# fpga_eagle_1.net
KiCad netlist of a schematic drawn in Altium Designer
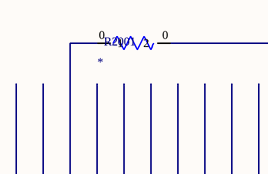
[diagram p0: fpga_eagle_1.SchDoc, top left]
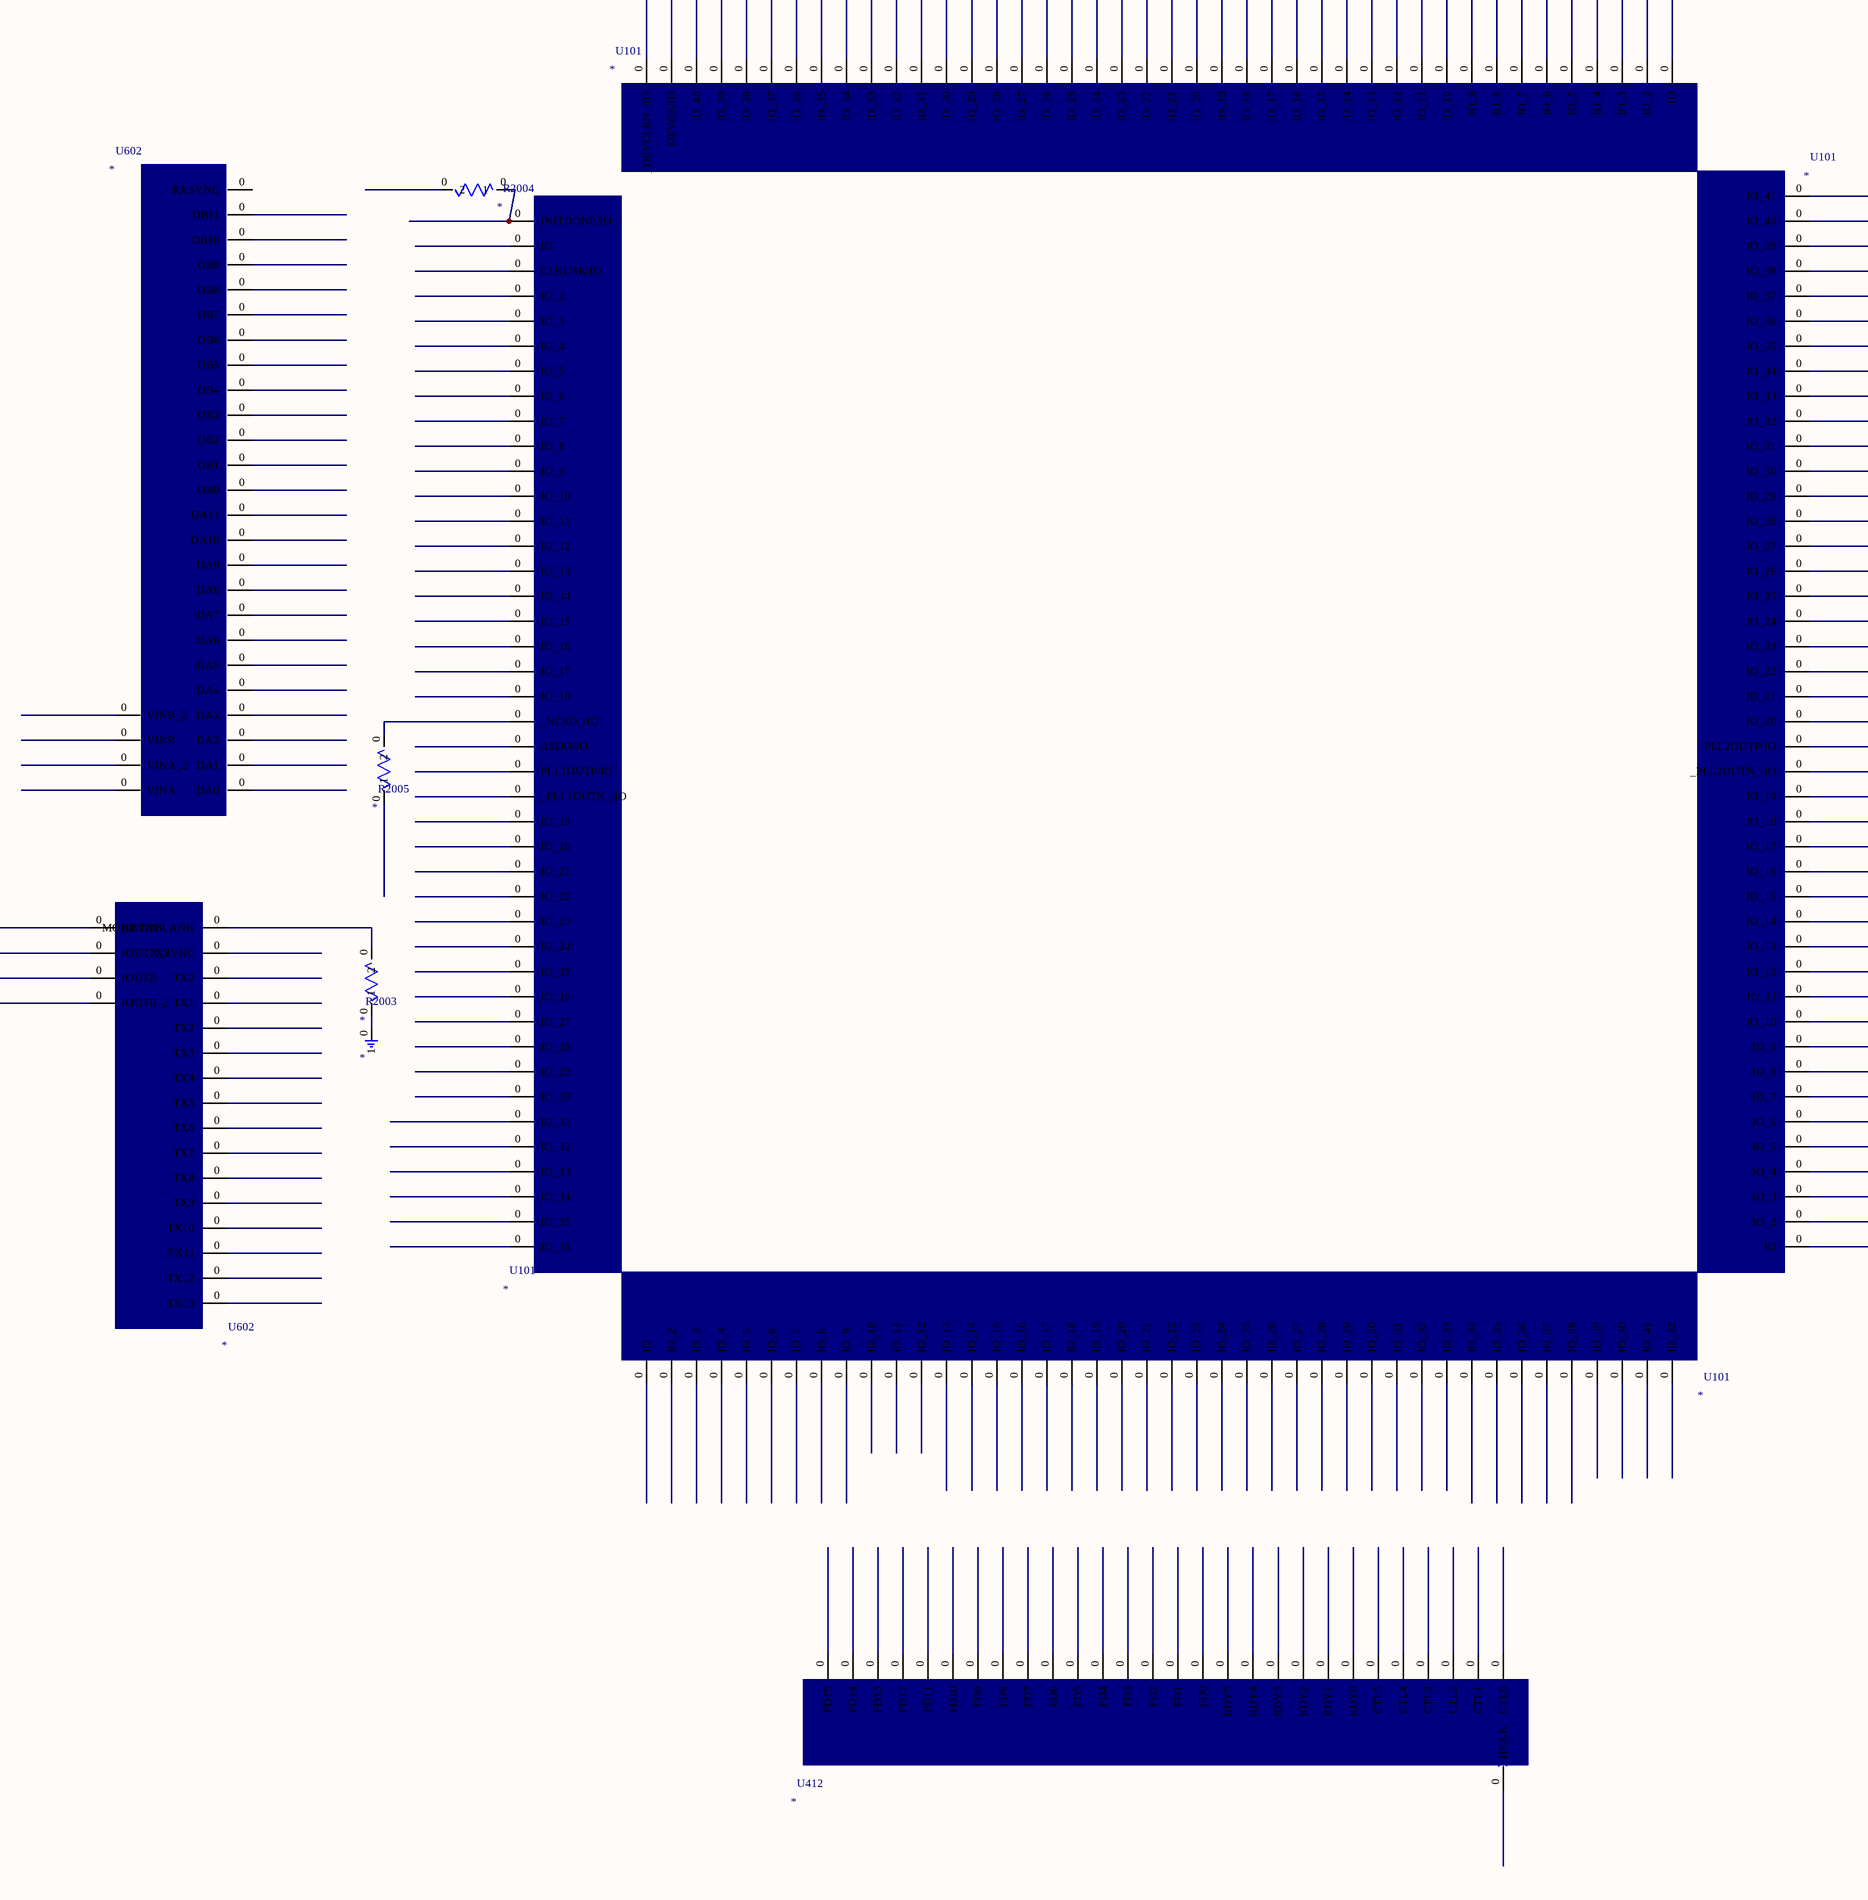
[diagram p1: fpga_eagle_1.SchDoc, bottom left]
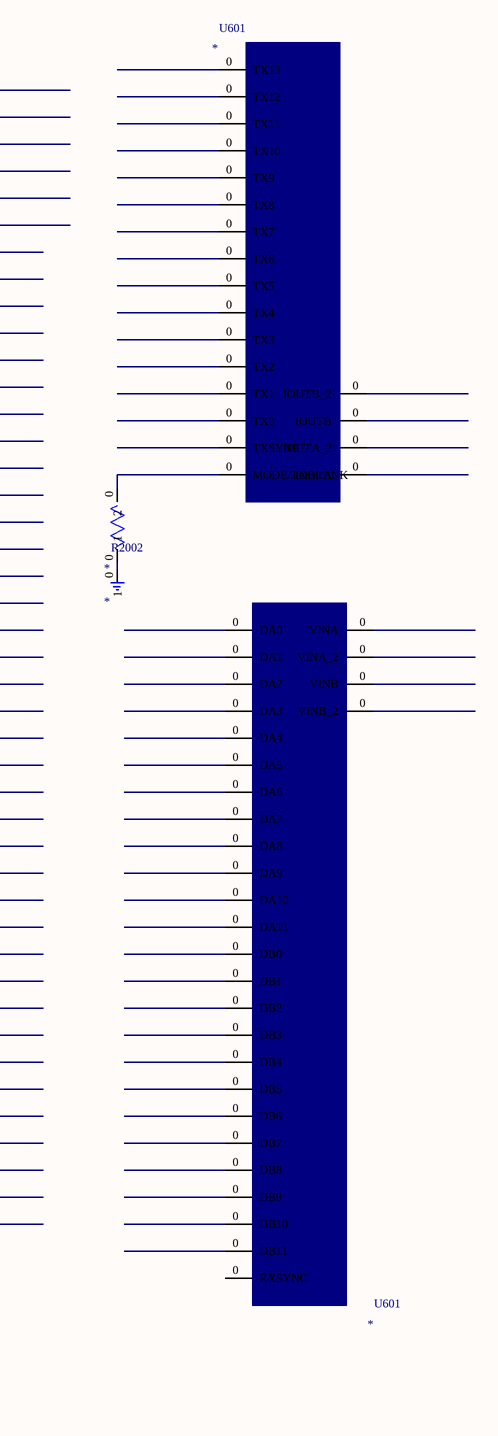
[diagram p2: fpga_eagle_1.SchDoc, bottom right]

(export (version "E")
  (design (tool "Eeschema 10.0.6"))
  (components
    (comp (ref "GND-1") (value "*") (libsource (lib "openjson") (part "GND-1")))
    (comp (ref "GND-1-5") (value "*") (libsource (lib "openjson") (part "GND-1")))
    (comp (ref "R2001") (value "*") (libsource (lib "openjson") (part "RESISTOR-1")))
    (comp (ref "R2002") (value "*") (libsource (lib "") (part "RESISTOR-1_MIRRORED_2")))
    (comp (ref "R2003") (value "*") (libsource (lib "") (part "RESISTOR-1_MIRRORED_3")))
    (comp (ref "R2004") (value "*") (libsource (lib "openjson") (part "RESISTOR-1_MIRRORED")))
    (comp (ref "R2005") (value "*") (libsource (lib "") (part "RESISTOR-1_MIRRORED_1")))
    (comp (ref "U101") (value "*") (libsource (lib "openjson") (part "EP1C12-PQ240-IO1")))
    (comp (ref "U101-1") (value "*") (libsource (lib "openjson") (part "EP1C12-PQ240-IO2")))
    (comp (ref "U101-2") (value "*") (libsource (lib "openjson") (part "EP1C12-PQ240-IO3")))
    (comp (ref "U101-3") (value "*") (libsource (lib "openjson") (part "EP1C12-PQ240-IO4")))
    (comp (ref "U412") (value "*") (libsource (lib "openjson") (part "CY7C68013-TQ100-BUS_MIRRORED")))
    (comp (ref "U601") (value "*") (libsource (lib "openjson") (part "AD986X-RX_MIRRORED")))
    (comp (ref "U601-0") (value "*") (libsource (lib "openjson") (part "AD986X-TX_MIRRORED")))
    (comp (ref "U602") (value "*") (libsource (lib "") (part "AD986X-RX_MIRRORED_1")))
    (comp (ref "U602-4") (value "*") (libsource (lib "") (part "AD986X-TX_MIRRORED_1")))
  )
  (nets
    (net (code "1") (name "Net-(GND-1-1)") (class "Default")
      (node (ref "GND-1") (pin "0") (pinfunction "1_0") (pintype "passive"))
      (node (ref "R2003") (pin "0") (pinfunction "1_0") (pintype "passive"))
    )
    (net (code "2") (name "Net-(GND-1-5-1)") (class "Default")
      (node (ref "GND-1-5") (pin "0") (pinfunction "1_0") (pintype "passive"))
      (node (ref "R2002") (pin "0") (pinfunction "1_0") (pintype "passive"))
    )
    (net (code "3") (name "Net-(R2001-1)") (class "Default")
      (node (ref "R2001") (pin "0") (pinfunction "1_0") (pintype "passive"))
      (node (ref "U101-1") (pin "0") (pinfunction "IO_10_0") (pintype "passive"))
    )
    (net (code "4") (name "Net-(R2002-2)") (class "Default")
      (node (ref "R2002") (pin "0") (pinfunction "2_0") (pintype "passive"))
      (node (ref "U601-0") (pin "0") (pinfunction "MODE/TXBLANK_0") (pintype "passive"))
    )
    (net (code "5") (name "Net-(R2003-2)") (class "Default")
      (node (ref "R2003") (pin "0") (pinfunction "2_0") (pintype "passive"))
      (node (ref "U602-4") (pin "0") (pinfunction "MODE/TXBLANK_0") (pintype "passive"))
    )
    (net (code "6") (name "Net-(R2004-1)") (class "Default")
      (node (ref "R2004") (pin "0") (pinfunction "1_0") (pintype "passive"))
      (node (ref "U101") (pin "0") (pinfunction "INITDONE/IO_0") (pintype "passive"))
    )
    (net (code "7") (name "Net-(R2005-2)") (class "Default")
      (node (ref "R2005") (pin "0") (pinfunction "2_0") (pintype "passive"))
      (node (ref "U101") (pin "0") (pinfunction "_NCSO_/IO_0") (pintype "passive"))
    )
    (net (code "8") (name "unconnected-(R2001-2-Pad0)") (class "Default")
      (node (ref "R2001") (pin "0") (pinfunction "2_0") (pintype "passive"))
    )
    (net (code "9") (name "unconnected-(R2004-2-Pad0)") (class "Default")
      (node (ref "R2004") (pin "0") (pinfunction "2_0") (pintype "passive"))
    )
    (net (code "10") (name "unconnected-(R2005-1-Pad0)") (class "Default")
      (node (ref "R2005") (pin "0") (pinfunction "1_0") (pintype "passive"))
    )
    (net (code "11") (name "unconnected-(U101-1-DEVOE{slash}IO-Pad0)") (class "Default")
      (node (ref "U101-1") (pin "0") (pinfunction "DEVOE/IO_0") (pintype "passive"))
    )
    (net (code "12") (name "unconnected-(U101-1-IO-Pad0)") (class "Default")
      (node (ref "U101-1") (pin "0") (pinfunction "IO_0") (pintype "passive"))
    )
    (net (code "13") (name "unconnected-(U101-1-IO_2-Pad0)") (class "Default")
      (node (ref "U101-1") (pin "0") (pinfunction "IO_2_0") (pintype "passive"))
    )
    (net (code "14") (name "unconnected-(U101-1-IO_3-Pad0)") (class "Default")
      (node (ref "U101-1") (pin "0") (pinfunction "IO_3_0") (pintype "passive"))
    )
    (net (code "15") (name "unconnected-(U101-1-IO_4-Pad0)") (class "Default")
      (node (ref "U101-1") (pin "0") (pinfunction "IO_4_0") (pintype "passive"))
    )
    (net (code "16") (name "unconnected-(U101-1-IO_5-Pad0)") (class "Default")
      (node (ref "U101-1") (pin "0") (pinfunction "IO_5_0") (pintype "passive"))
    )
    (net (code "17") (name "unconnected-(U101-1-IO_6-Pad0)") (class "Default")
      (node (ref "U101-1") (pin "0") (pinfunction "IO_6_0") (pintype "passive"))
    )
    (net (code "18") (name "unconnected-(U101-1-IO_7-Pad0)") (class "Default")
      (node (ref "U101-1") (pin "0") (pinfunction "IO_7_0") (pintype "passive"))
    )
    (net (code "19") (name "unconnected-(U101-1-IO_8-Pad0)") (class "Default")
      (node (ref "U101-1") (pin "0") (pinfunction "IO_8_0") (pintype "passive"))
    )
    (net (code "20") (name "unconnected-(U101-1-IO_9-Pad0)") (class "Default")
      (node (ref "U101-1") (pin "0") (pinfunction "IO_9_0") (pintype "passive"))
    )
    (net (code "21") (name "unconnected-(U101-1-IO_11-Pad0)") (class "Default")
      (node (ref "U101-1") (pin "0") (pinfunction "IO_11_0") (pintype "passive"))
    )
    (net (code "22") (name "unconnected-(U101-1-IO_12-Pad0)") (class "Default")
      (node (ref "U101-1") (pin "0") (pinfunction "IO_12_0") (pintype "passive"))
    )
    (net (code "23") (name "unconnected-(U101-1-IO_13-Pad0)") (class "Default")
      (node (ref "U101-1") (pin "0") (pinfunction "IO_13_0") (pintype "passive"))
    )
    (net (code "24") (name "unconnected-(U101-1-IO_14-Pad0)") (class "Default")
      (node (ref "U101-1") (pin "0") (pinfunction "IO_14_0") (pintype "passive"))
    )
    (net (code "25") (name "unconnected-(U101-1-IO_15-Pad0)") (class "Default")
      (node (ref "U101-1") (pin "0") (pinfunction "IO_15_0") (pintype "passive"))
    )
    (net (code "26") (name "unconnected-(U101-1-IO_16-Pad0)") (class "Default")
      (node (ref "U101-1") (pin "0") (pinfunction "IO_16_0") (pintype "passive"))
    )
    (net (code "27") (name "unconnected-(U101-1-IO_17-Pad0)") (class "Default")
      (node (ref "U101-1") (pin "0") (pinfunction "IO_17_0") (pintype "passive"))
    )
    (net (code "28") (name "unconnected-(U101-1-IO_18-Pad0)") (class "Default")
      (node (ref "U101-1") (pin "0") (pinfunction "IO_18_0") (pintype "passive"))
    )
    (net (code "29") (name "unconnected-(U101-1-IO_19-Pad0)") (class "Default")
      (node (ref "U101-1") (pin "0") (pinfunction "IO_19_0") (pintype "passive"))
    )
    (net (code "30") (name "unconnected-(U101-1-IO_20-Pad0)") (class "Default")
      (node (ref "U101-1") (pin "0") (pinfunction "IO_20_0") (pintype "passive"))
    )
    (net (code "31") (name "unconnected-(U101-1-IO_21-Pad0)") (class "Default")
      (node (ref "U101-1") (pin "0") (pinfunction "IO_21_0") (pintype "passive"))
    )
    (net (code "32") (name "unconnected-(U101-1-IO_22-Pad0)") (class "Default")
      (node (ref "U101-1") (pin "0") (pinfunction "IO_22_0") (pintype "passive"))
    )
    (net (code "33") (name "unconnected-(U101-1-IO_23-Pad0)") (class "Default")
      (node (ref "U101-1") (pin "0") (pinfunction "IO_23_0") (pintype "passive"))
    )
    (net (code "34") (name "unconnected-(U101-1-IO_24-Pad0)") (class "Default")
      (node (ref "U101-1") (pin "0") (pinfunction "IO_24_0") (pintype "passive"))
    )
    (net (code "35") (name "unconnected-(U101-1-IO_25-Pad0)") (class "Default")
      (node (ref "U101-1") (pin "0") (pinfunction "IO_25_0") (pintype "passive"))
    )
    (net (code "36") (name "unconnected-(U101-1-IO_26-Pad0)") (class "Default")
      (node (ref "U101-1") (pin "0") (pinfunction "IO_26_0") (pintype "passive"))
    )
    (net (code "37") (name "unconnected-(U101-1-IO_27-Pad0)") (class "Default")
      (node (ref "U101-1") (pin "0") (pinfunction "IO_27_0") (pintype "passive"))
    )
    (net (code "38") (name "unconnected-(U101-1-IO_28-Pad0)") (class "Default")
      (node (ref "U101-1") (pin "0") (pinfunction "IO_28_0") (pintype "passive"))
    )
    (net (code "39") (name "unconnected-(U101-1-IO_29-Pad0)") (class "Default")
      (node (ref "U101-1") (pin "0") (pinfunction "IO_29_0") (pintype "passive"))
    )
    (net (code "40") (name "unconnected-(U101-1-IO_30-Pad0)") (class "Default")
      (node (ref "U101-1") (pin "0") (pinfunction "IO_30_0") (pintype "passive"))
    )
    (net (code "41") (name "unconnected-(U101-1-IO_31-Pad0)") (class "Default")
      (node (ref "U101-1") (pin "0") (pinfunction "IO_31_0") (pintype "passive"))
    )
    (net (code "42") (name "unconnected-(U101-1-IO_32-Pad0)") (class "Default")
      (node (ref "U101-1") (pin "0") (pinfunction "IO_32_0") (pintype "passive"))
    )
    (net (code "43") (name "unconnected-(U101-1-IO_33-Pad0)") (class "Default")
      (node (ref "U101-1") (pin "0") (pinfunction "IO_33_0") (pintype "passive"))
    )
    (net (code "44") (name "unconnected-(U101-1-IO_34-Pad0)") (class "Default")
      (node (ref "U101-1") (pin "0") (pinfunction "IO_34_0") (pintype "passive"))
    )
    (net (code "45") (name "unconnected-(U101-1-IO_35-Pad0)") (class "Default")
      (node (ref "U101-1") (pin "0") (pinfunction "IO_35_0") (pintype "passive"))
    )
    (net (code "46") (name "unconnected-(U101-1-IO_36-Pad0)") (class "Default")
      (node (ref "U101-1") (pin "0") (pinfunction "IO_36_0") (pintype "passive"))
    )
    (net (code "47") (name "unconnected-(U101-1-IO_37-Pad0)") (class "Default")
      (node (ref "U101-1") (pin "0") (pinfunction "IO_37_0") (pintype "passive"))
    )
    (net (code "48") (name "unconnected-(U101-1-IO_38-Pad0)") (class "Default")
      (node (ref "U101-1") (pin "0") (pinfunction "IO_38_0") (pintype "passive"))
    )
    (net (code "49") (name "unconnected-(U101-1-IO_39-Pad0)") (class "Default")
      (node (ref "U101-1") (pin "0") (pinfunction "IO_39_0") (pintype "passive"))
    )
    (net (code "50") (name "unconnected-(U101-1-IO_40-Pad0)") (class "Default")
      (node (ref "U101-1") (pin "0") (pinfunction "IO_40_0") (pintype "passive"))
    )
    (net (code "51") (name "unconnected-(U101-1-_DE~{V}CLRN_{slash}IO-Pad0)") (class "Default")
      (node (ref "U101-1") (pin "0") (pinfunction "_DE~{V}CLRN_/IO_0") (pintype "passive"))
    )
    (net (code "52") (name "unconnected-(U101-2-IO-Pad0)") (class "Default")
      (node (ref "U101-2") (pin "0") (pinfunction "IO_0") (pintype "passive"))
    )
    (net (code "53") (name "unconnected-(U101-2-IO_2-Pad0)") (class "Default")
      (node (ref "U101-2") (pin "0") (pinfunction "IO_2_0") (pintype "passive"))
    )
    (net (code "54") (name "unconnected-(U101-2-IO_3-Pad0)") (class "Default")
      (node (ref "U101-2") (pin "0") (pinfunction "IO_3_0") (pintype "passive"))
    )
    (net (code "55") (name "unconnected-(U101-2-IO_4-Pad0)") (class "Default")
      (node (ref "U101-2") (pin "0") (pinfunction "IO_4_0") (pintype "passive"))
    )
    (net (code "56") (name "unconnected-(U101-2-IO_5-Pad0)") (class "Default")
      (node (ref "U101-2") (pin "0") (pinfunction "IO_5_0") (pintype "passive"))
    )
    (net (code "57") (name "unconnected-(U101-2-IO_6-Pad0)") (class "Default")
      (node (ref "U101-2") (pin "0") (pinfunction "IO_6_0") (pintype "passive"))
    )
    (net (code "58") (name "unconnected-(U101-2-IO_7-Pad0)") (class "Default")
      (node (ref "U101-2") (pin "0") (pinfunction "IO_7_0") (pintype "passive"))
    )
    (net (code "59") (name "unconnected-(U101-2-IO_8-Pad0)") (class "Default")
      (node (ref "U101-2") (pin "0") (pinfunction "IO_8_0") (pintype "passive"))
    )
    (net (code "60") (name "unconnected-(U101-2-IO_9-Pad0)") (class "Default")
      (node (ref "U101-2") (pin "0") (pinfunction "IO_9_0") (pintype "passive"))
    )
    (net (code "61") (name "unconnected-(U101-2-IO_10-Pad0)") (class "Default")
      (node (ref "U101-2") (pin "0") (pinfunction "IO_10_0") (pintype "passive"))
    )
    (net (code "62") (name "unconnected-(U101-2-IO_11-Pad0)") (class "Default")
      (node (ref "U101-2") (pin "0") (pinfunction "IO_11_0") (pintype "passive"))
    )
    (net (code "63") (name "unconnected-(U101-2-IO_12-Pad0)") (class "Default")
      (node (ref "U101-2") (pin "0") (pinfunction "IO_12_0") (pintype "passive"))
    )
    (net (code "64") (name "unconnected-(U101-2-IO_13-Pad0)") (class "Default")
      (node (ref "U101-2") (pin "0") (pinfunction "IO_13_0") (pintype "passive"))
    )
    (net (code "65") (name "unconnected-(U101-2-IO_14-Pad0)") (class "Default")
      (node (ref "U101-2") (pin "0") (pinfunction "IO_14_0") (pintype "passive"))
    )
    (net (code "66") (name "unconnected-(U101-2-IO_15-Pad0)") (class "Default")
      (node (ref "U101-2") (pin "0") (pinfunction "IO_15_0") (pintype "passive"))
    )
    (net (code "67") (name "unconnected-(U101-2-IO_16-Pad0)") (class "Default")
      (node (ref "U101-2") (pin "0") (pinfunction "IO_16_0") (pintype "passive"))
    )
    (net (code "68") (name "unconnected-(U101-2-IO_17-Pad0)") (class "Default")
      (node (ref "U101-2") (pin "0") (pinfunction "IO_17_0") (pintype "passive"))
    )
    (net (code "69") (name "unconnected-(U101-2-IO_18-Pad0)") (class "Default")
      (node (ref "U101-2") (pin "0") (pinfunction "IO_18_0") (pintype "passive"))
    )
    (net (code "70") (name "unconnected-(U101-2-IO_19-Pad0)") (class "Default")
      (node (ref "U101-2") (pin "0") (pinfunction "IO_19_0") (pintype "passive"))
    )
    (net (code "71") (name "unconnected-(U101-2-IO_20-Pad0)") (class "Default")
      (node (ref "U101-2") (pin "0") (pinfunction "IO_20_0") (pintype "passive"))
    )
    (net (code "72") (name "unconnected-(U101-2-IO_21-Pad0)") (class "Default")
      (node (ref "U101-2") (pin "0") (pinfunction "IO_21_0") (pintype "passive"))
    )
    (net (code "73") (name "unconnected-(U101-2-IO_22-Pad0)") (class "Default")
      (node (ref "U101-2") (pin "0") (pinfunction "IO_22_0") (pintype "passive"))
    )
    (net (code "74") (name "unconnected-(U101-2-IO_23-Pad0)") (class "Default")
      (node (ref "U101-2") (pin "0") (pinfunction "IO_23_0") (pintype "passive"))
    )
    (net (code "75") (name "unconnected-(U101-2-IO_24-Pad0)") (class "Default")
      (node (ref "U101-2") (pin "0") (pinfunction "IO_24_0") (pintype "passive"))
    )
    (net (code "76") (name "unconnected-(U101-2-IO_25-Pad0)") (class "Default")
      (node (ref "U101-2") (pin "0") (pinfunction "IO_25_0") (pintype "passive"))
    )
    (net (code "77") (name "unconnected-(U101-2-IO_26-Pad0)") (class "Default")
      (node (ref "U101-2") (pin "0") (pinfunction "IO_26_0") (pintype "passive"))
    )
    (net (code "78") (name "unconnected-(U101-2-IO_27-Pad0)") (class "Default")
      (node (ref "U101-2") (pin "0") (pinfunction "IO_27_0") (pintype "passive"))
    )
    (net (code "79") (name "unconnected-(U101-2-IO_28-Pad0)") (class "Default")
      (node (ref "U101-2") (pin "0") (pinfunction "IO_28_0") (pintype "passive"))
    )
    (net (code "80") (name "unconnected-(U101-2-IO_29-Pad0)") (class "Default")
      (node (ref "U101-2") (pin "0") (pinfunction "IO_29_0") (pintype "passive"))
    )
    (net (code "81") (name "unconnected-(U101-2-IO_30-Pad0)") (class "Default")
      (node (ref "U101-2") (pin "0") (pinfunction "IO_30_0") (pintype "passive"))
    )
    (net (code "82") (name "unconnected-(U101-2-IO_31-Pad0)") (class "Default")
      (node (ref "U101-2") (pin "0") (pinfunction "IO_31_0") (pintype "passive"))
    )
    (net (code "83") (name "unconnected-(U101-2-IO_32-Pad0)") (class "Default")
      (node (ref "U101-2") (pin "0") (pinfunction "IO_32_0") (pintype "passive"))
    )
    (net (code "84") (name "unconnected-(U101-2-IO_33-Pad0)") (class "Default")
      (node (ref "U101-2") (pin "0") (pinfunction "IO_33_0") (pintype "passive"))
    )
    (net (code "85") (name "unconnected-(U101-2-IO_34-Pad0)") (class "Default")
      (node (ref "U101-2") (pin "0") (pinfunction "IO_34_0") (pintype "passive"))
    )
    (net (code "86") (name "unconnected-(U101-2-IO_35-Pad0)") (class "Default")
      (node (ref "U101-2") (pin "0") (pinfunction "IO_35_0") (pintype "passive"))
    )
    (net (code "87") (name "unconnected-(U101-2-IO_36-Pad0)") (class "Default")
      (node (ref "U101-2") (pin "0") (pinfunction "IO_36_0") (pintype "passive"))
    )
    (net (code "88") (name "unconnected-(U101-2-IO_37-Pad0)") (class "Default")
      (node (ref "U101-2") (pin "0") (pinfunction "IO_37_0") (pintype "passive"))
    )
    (net (code "89") (name "unconnected-(U101-2-IO_38-Pad0)") (class "Default")
      (node (ref "U101-2") (pin "0") (pinfunction "IO_38_0") (pintype "passive"))
    )
    (net (code "90") (name "unconnected-(U101-2-IO_39-Pad0)") (class "Default")
      (node (ref "U101-2") (pin "0") (pinfunction "IO_39_0") (pintype "passive"))
    )
    (net (code "91") (name "unconnected-(U101-2-IO_40-Pad0)") (class "Default")
      (node (ref "U101-2") (pin "0") (pinfunction "IO_40_0") (pintype "passive"))
    )
    (net (code "92") (name "unconnected-(U101-2-IO_41-Pad0)") (class "Default")
      (node (ref "U101-2") (pin "0") (pinfunction "IO_41_0") (pintype "passive"))
    )
    (net (code "93") (name "unconnected-(U101-2-PLL2OUTP{slash}IO-Pad0)") (class "Default")
      (node (ref "U101-2") (pin "0") (pinfunction "PLL2OUTP/IO_0") (pintype "passive"))
    )
    (net (code "94") (name "unconnected-(U101-2-_PLL2OUTN_{slash}IO-Pad0)") (class "Default")
      (node (ref "U101-2") (pin "0") (pinfunction "_PLL2OUTN_/IO_0") (pintype "passive"))
    )
    (net (code "95") (name "unconnected-(U101-3-IO-Pad0)") (class "Default")
      (node (ref "U101-3") (pin "0") (pinfunction "IO_0") (pintype "passive"))
    )
    (net (code "96") (name "unconnected-(U101-3-IO_2-Pad0)") (class "Default")
      (node (ref "U101-3") (pin "0") (pinfunction "IO_2_0") (pintype "passive"))
    )
    (net (code "97") (name "unconnected-(U101-3-IO_3-Pad0)") (class "Default")
      (node (ref "U101-3") (pin "0") (pinfunction "IO_3_0") (pintype "passive"))
    )
    (net (code "98") (name "unconnected-(U101-3-IO_4-Pad0)") (class "Default")
      (node (ref "U101-3") (pin "0") (pinfunction "IO_4_0") (pintype "passive"))
    )
    (net (code "99") (name "unconnected-(U101-3-IO_5-Pad0)") (class "Default")
      (node (ref "U101-3") (pin "0") (pinfunction "IO_5_0") (pintype "passive"))
    )
    (net (code "100") (name "unconnected-(U101-3-IO_6-Pad0)") (class "Default")
      (node (ref "U101-3") (pin "0") (pinfunction "IO_6_0") (pintype "passive"))
    )
    (net (code "101") (name "unconnected-(U101-3-IO_7-Pad0)") (class "Default")
      (node (ref "U101-3") (pin "0") (pinfunction "IO_7_0") (pintype "passive"))
    )
    (net (code "102") (name "unconnected-(U101-3-IO_8-Pad0)") (class "Default")
      (node (ref "U101-3") (pin "0") (pinfunction "IO_8_0") (pintype "passive"))
    )
    (net (code "103") (name "unconnected-(U101-3-IO_9-Pad0)") (class "Default")
      (node (ref "U101-3") (pin "0") (pinfunction "IO_9_0") (pintype "passive"))
    )
    (net (code "104") (name "unconnected-(U101-3-IO_10-Pad0)") (class "Default")
      (node (ref "U101-3") (pin "0") (pinfunction "IO_10_0") (pintype "passive"))
    )
    (net (code "105") (name "unconnected-(U101-3-IO_11-Pad0)") (class "Default")
      (node (ref "U101-3") (pin "0") (pinfunction "IO_11_0") (pintype "passive"))
    )
    (net (code "106") (name "unconnected-(U101-3-IO_12-Pad0)") (class "Default")
      (node (ref "U101-3") (pin "0") (pinfunction "IO_12_0") (pintype "passive"))
    )
    (net (code "107") (name "unconnected-(U101-3-IO_13-Pad0)") (class "Default")
      (node (ref "U101-3") (pin "0") (pinfunction "IO_13_0") (pintype "passive"))
    )
    (net (code "108") (name "unconnected-(U101-3-IO_14-Pad0)") (class "Default")
      (node (ref "U101-3") (pin "0") (pinfunction "IO_14_0") (pintype "passive"))
    )
    (net (code "109") (name "unconnected-(U101-3-IO_15-Pad0)") (class "Default")
      (node (ref "U101-3") (pin "0") (pinfunction "IO_15_0") (pintype "passive"))
    )
    (net (code "110") (name "unconnected-(U101-3-IO_16-Pad0)") (class "Default")
      (node (ref "U101-3") (pin "0") (pinfunction "IO_16_0") (pintype "passive"))
    )
    (net (code "111") (name "unconnected-(U101-3-IO_17-Pad0)") (class "Default")
      (node (ref "U101-3") (pin "0") (pinfunction "IO_17_0") (pintype "passive"))
    )
    (net (code "112") (name "unconnected-(U101-3-IO_18-Pad0)") (class "Default")
      (node (ref "U101-3") (pin "0") (pinfunction "IO_18_0") (pintype "passive"))
    )
    (net (code "113") (name "unconnected-(U101-3-IO_19-Pad0)") (class "Default")
      (node (ref "U101-3") (pin "0") (pinfunction "IO_19_0") (pintype "passive"))
    )
    (net (code "114") (name "unconnected-(U101-3-IO_20-Pad0)") (class "Default")
      (node (ref "U101-3") (pin "0") (pinfunction "IO_20_0") (pintype "passive"))
    )
    (net (code "115") (name "unconnected-(U101-3-IO_21-Pad0)") (class "Default")
      (node (ref "U101-3") (pin "0") (pinfunction "IO_21_0") (pintype "passive"))
    )
    (net (code "116") (name "unconnected-(U101-3-IO_22-Pad0)") (class "Default")
      (node (ref "U101-3") (pin "0") (pinfunction "IO_22_0") (pintype "passive"))
    )
    (net (code "117") (name "unconnected-(U101-3-IO_23-Pad0)") (class "Default")
      (node (ref "U101-3") (pin "0") (pinfunction "IO_23_0") (pintype "passive"))
    )
    (net (code "118") (name "unconnected-(U101-3-IO_24-Pad0)") (class "Default")
      (node (ref "U101-3") (pin "0") (pinfunction "IO_24_0") (pintype "passive"))
    )
    (net (code "119") (name "unconnected-(U101-3-IO_25-Pad0)") (class "Default")
      (node (ref "U101-3") (pin "0") (pinfunction "IO_25_0") (pintype "passive"))
    )
    (net (code "120") (name "unconnected-(U101-3-IO_26-Pad0)") (class "Default")
      (node (ref "U101-3") (pin "0") (pinfunction "IO_26_0") (pintype "passive"))
    )
    (net (code "121") (name "unconnected-(U101-3-IO_27-Pad0)") (class "Default")
      (node (ref "U101-3") (pin "0") (pinfunction "IO_27_0") (pintype "passive"))
    )
    (net (code "122") (name "unconnected-(U101-3-IO_28-Pad0)") (class "Default")
      (node (ref "U101-3") (pin "0") (pinfunction "IO_28_0") (pintype "passive"))
    )
    (net (code "123") (name "unconnected-(U101-3-IO_29-Pad0)") (class "Default")
      (node (ref "U101-3") (pin "0") (pinfunction "IO_29_0") (pintype "passive"))
    )
    (net (code "124") (name "unconnected-(U101-3-IO_30-Pad0)") (class "Default")
      (node (ref "U101-3") (pin "0") (pinfunction "IO_30_0") (pintype "passive"))
    )
    (net (code "125") (name "unconnected-(U101-3-IO_31-Pad0)") (class "Default")
      (node (ref "U101-3") (pin "0") (pinfunction "IO_31_0") (pintype "passive"))
    )
    (net (code "126") (name "unconnected-(U101-3-IO_32-Pad0)") (class "Default")
      (node (ref "U101-3") (pin "0") (pinfunction "IO_32_0") (pintype "passive"))
    )
    (net (code "127") (name "unconnected-(U101-3-IO_33-Pad0)") (class "Default")
      (node (ref "U101-3") (pin "0") (pinfunction "IO_33_0") (pintype "passive"))
    )
    (net (code "128") (name "unconnected-(U101-3-IO_34-Pad0)") (class "Default")
      (node (ref "U101-3") (pin "0") (pinfunction "IO_34_0") (pintype "passive"))
    )
    (net (code "129") (name "unconnected-(U101-3-IO_35-Pad0)") (class "Default")
      (node (ref "U101-3") (pin "0") (pinfunction "IO_35_0") (pintype "passive"))
    )
    (net (code "130") (name "unconnected-(U101-3-IO_36-Pad0)") (class "Default")
      (node (ref "U101-3") (pin "0") (pinfunction "IO_36_0") (pintype "passive"))
    )
    (net (code "131") (name "unconnected-(U101-3-IO_37-Pad0)") (class "Default")
      (node (ref "U101-3") (pin "0") (pinfunction "IO_37_0") (pintype "passive"))
    )
    (net (code "132") (name "unconnected-(U101-3-IO_38-Pad0)") (class "Default")
      (node (ref "U101-3") (pin "0") (pinfunction "IO_38_0") (pintype "passive"))
    )
    (net (code "133") (name "unconnected-(U101-3-IO_39-Pad0)") (class "Default")
      (node (ref "U101-3") (pin "0") (pinfunction "IO_39_0") (pintype "passive"))
    )
    (net (code "134") (name "unconnected-(U101-3-IO_40-Pad0)") (class "Default")
      (node (ref "U101-3") (pin "0") (pinfunction "IO_40_0") (pintype "passive"))
    )
    (net (code "135") (name "unconnected-(U101-3-IO_41-Pad0)") (class "Default")
      (node (ref "U101-3") (pin "0") (pinfunction "IO_41_0") (pintype "passive"))
    )
    (net (code "136") (name "unconnected-(U101-3-IO_42-Pad0)") (class "Default")
      (node (ref "U101-3") (pin "0") (pinfunction "IO_42_0") (pintype "passive"))
    )
    (net (code "137") (name "unconnected-(U101-ASDO{slash}IO-Pad0)") (class "Default")
      (node (ref "U101") (pin "0") (pinfunction "ASDO/IO_0") (pintype "passive"))
    )
    (net (code "138") (name "unconnected-(U101-CLKUSR{slash}IO-Pad0)") (class "Default")
      (node (ref "U101") (pin "0") (pinfunction "CLKUSR/IO_0") (pintype "passive"))
    )
    (net (code "139") (name "unconnected-(U101-IO-Pad0)") (class "Default")
      (node (ref "U101") (pin "0") (pinfunction "IO_0") (pintype "passive"))
    )
    (net (code "140") (name "unconnected-(U101-IO_2-Pad0)") (class "Default")
      (node (ref "U101") (pin "0") (pinfunction "IO_2_0") (pintype "passive"))
    )
    (net (code "141") (name "unconnected-(U101-IO_3-Pad0)") (class "Default")
      (node (ref "U101") (pin "0") (pinfunction "IO_3_0") (pintype "passive"))
    )
    (net (code "142") (name "unconnected-(U101-IO_4-Pad0)") (class "Default")
      (node (ref "U101") (pin "0") (pinfunction "IO_4_0") (pintype "passive"))
    )
    (net (code "143") (name "unconnected-(U101-IO_5-Pad0)") (class "Default")
      (node (ref "U101") (pin "0") (pinfunction "IO_5_0") (pintype "passive"))
    )
    (net (code "144") (name "unconnected-(U101-IO_6-Pad0)") (class "Default")
      (node (ref "U101") (pin "0") (pinfunction "IO_6_0") (pintype "passive"))
    )
    (net (code "145") (name "unconnected-(U101-IO_7-Pad0)") (class "Default")
      (node (ref "U101") (pin "0") (pinfunction "IO_7_0") (pintype "passive"))
    )
    (net (code "146") (name "unconnected-(U101-IO_8-Pad0)") (class "Default")
      (node (ref "U101") (pin "0") (pinfunction "IO_8_0") (pintype "passive"))
    )
    (net (code "147") (name "unconnected-(U101-IO_9-Pad0)") (class "Default")
      (node (ref "U101") (pin "0") (pinfunction "IO_9_0") (pintype "passive"))
    )
    (net (code "148") (name "unconnected-(U101-IO_10-Pad0)") (class "Default")
      (node (ref "U101") (pin "0") (pinfunction "IO_10_0") (pintype "passive"))
    )
    (net (code "149") (name "unconnected-(U101-IO_11-Pad0)") (class "Default")
      (node (ref "U101") (pin "0") (pinfunction "IO_11_0") (pintype "passive"))
    )
    (net (code "150") (name "unconnected-(U101-IO_12-Pad0)") (class "Default")
      (node (ref "U101") (pin "0") (pinfunction "IO_12_0") (pintype "passive"))
    )
    (net (code "151") (name "unconnected-(U101-IO_13-Pad0)") (class "Default")
      (node (ref "U101") (pin "0") (pinfunction "IO_13_0") (pintype "passive"))
    )
    (net (code "152") (name "unconnected-(U101-IO_14-Pad0)") (class "Default")
      (node (ref "U101") (pin "0") (pinfunction "IO_14_0") (pintype "passive"))
    )
    (net (code "153") (name "unconnected-(U101-IO_15-Pad0)") (class "Default")
      (node (ref "U101") (pin "0") (pinfunction "IO_15_0") (pintype "passive"))
    )
    (net (code "154") (name "unconnected-(U101-IO_16-Pad0)") (class "Default")
      (node (ref "U101") (pin "0") (pinfunction "IO_16_0") (pintype "passive"))
    )
    (net (code "155") (name "unconnected-(U101-IO_17-Pad0)") (class "Default")
      (node (ref "U101") (pin "0") (pinfunction "IO_17_0") (pintype "passive"))
    )
    (net (code "156") (name "unconnected-(U101-IO_18-Pad0)") (class "Default")
      (node (ref "U101") (pin "0") (pinfunction "IO_18_0") (pintype "passive"))
    )
    (net (code "157") (name "unconnected-(U101-IO_19-Pad0)") (class "Default")
      (node (ref "U101") (pin "0") (pinfunction "IO_19_0") (pintype "passive"))
    )
    (net (code "158") (name "unconnected-(U101-IO_20-Pad0)") (class "Default")
      (node (ref "U101") (pin "0") (pinfunction "IO_20_0") (pintype "passive"))
    )
    (net (code "159") (name "unconnected-(U101-IO_21-Pad0)") (class "Default")
      (node (ref "U101") (pin "0") (pinfunction "IO_21_0") (pintype "passive"))
    )
    (net (code "160") (name "unconnected-(U101-IO_22-Pad0)") (class "Default")
      (node (ref "U101") (pin "0") (pinfunction "IO_22_0") (pintype "passive"))
    )
    (net (code "161") (name "unconnected-(U101-IO_23-Pad0)") (class "Default")
      (node (ref "U101") (pin "0") (pinfunction "IO_23_0") (pintype "passive"))
    )
    (net (code "162") (name "unconnected-(U101-IO_24-Pad0)") (class "Default")
      (node (ref "U101") (pin "0") (pinfunction "IO_24_0") (pintype "passive"))
    )
    (net (code "163") (name "unconnected-(U101-IO_25-Pad0)") (class "Default")
      (node (ref "U101") (pin "0") (pinfunction "IO_25_0") (pintype "passive"))
    )
    (net (code "164") (name "unconnected-(U101-IO_26-Pad0)") (class "Default")
      (node (ref "U101") (pin "0") (pinfunction "IO_26_0") (pintype "passive"))
    )
    (net (code "165") (name "unconnected-(U101-IO_27-Pad0)") (class "Default")
      (node (ref "U101") (pin "0") (pinfunction "IO_27_0") (pintype "passive"))
    )
    (net (code "166") (name "unconnected-(U101-IO_28-Pad0)") (class "Default")
      (node (ref "U101") (pin "0") (pinfunction "IO_28_0") (pintype "passive"))
    )
    (net (code "167") (name "unconnected-(U101-IO_29-Pad0)") (class "Default")
      (node (ref "U101") (pin "0") (pinfunction "IO_29_0") (pintype "passive"))
    )
    (net (code "168") (name "unconnected-(U101-IO_30-Pad0)") (class "Default")
      (node (ref "U101") (pin "0") (pinfunction "IO_30_0") (pintype "passive"))
    )
    (net (code "169") (name "unconnected-(U101-IO_31-Pad0)") (class "Default")
      (node (ref "U101") (pin "0") (pinfunction "IO_31_0") (pintype "passive"))
    )
    (net (code "170") (name "unconnected-(U101-IO_32-Pad0)") (class "Default")
      (node (ref "U101") (pin "0") (pinfunction "IO_32_0") (pintype "passive"))
    )
    (net (code "171") (name "unconnected-(U101-IO_33-Pad0)") (class "Default")
      (node (ref "U101") (pin "0") (pinfunction "IO_33_0") (pintype "passive"))
    )
    (net (code "172") (name "unconnected-(U101-IO_34-Pad0)") (class "Default")
      (node (ref "U101") (pin "0") (pinfunction "IO_34_0") (pintype "passive"))
    )
    (net (code "173") (name "unconnected-(U101-IO_35-Pad0)") (class "Default")
      (node (ref "U101") (pin "0") (pinfunction "IO_35_0") (pintype "passive"))
    )
    (net (code "174") (name "unconnected-(U101-IO_36-Pad0)") (class "Default")
      (node (ref "U101") (pin "0") (pinfunction "IO_36_0") (pintype "passive"))
    )
    (net (code "175") (name "unconnected-(U101-PLL1OUTP{slash}IO-Pad0)") (class "Default")
      (node (ref "U101") (pin "0") (pinfunction "PLL1OUTP/IO_0") (pintype "passive"))
    )
    (net (code "176") (name "unconnected-(U101-_PLL1OUTN_{slash}IO-Pad0)") (class "Default")
      (node (ref "U101") (pin "0") (pinfunction "_PLL1OUTN_/IO_0") (pintype "passive"))
    )
    (net (code "177") (name "unconnected-(U412-CTL0-Pad0)") (class "Default")
      (node (ref "U412") (pin "0") (pinfunction "CTL0_0") (pintype "passive"))
    )
    (net (code "178") (name "unconnected-(U412-CTL1-Pad0)") (class "Default")
      (node (ref "U412") (pin "0") (pinfunction "CTL1_0") (pintype "passive"))
    )
    (net (code "179") (name "unconnected-(U412-CTL2-Pad0)") (class "Default")
      (node (ref "U412") (pin "0") (pinfunction "CTL2_0") (pintype "passive"))
    )
    (net (code "180") (name "unconnected-(U412-CTL3-Pad0)") (class "Default")
      (node (ref "U412") (pin "0") (pinfunction "CTL3_0") (pintype "passive"))
    )
    (net (code "181") (name "unconnected-(U412-CTL4-Pad0)") (class "Default")
      (node (ref "U412") (pin "0") (pinfunction "CTL4_0") (pintype "passive"))
    )
    (net (code "182") (name "unconnected-(U412-CTL5-Pad0)") (class "Default")
      (node (ref "U412") (pin "0") (pinfunction "CTL5_0") (pintype "passive"))
    )
    (net (code "183") (name "unconnected-(U412-FD0-Pad0)") (class "Default")
      (node (ref "U412") (pin "0") (pinfunction "FD0_0") (pintype "passive"))
    )
    (net (code "184") (name "unconnected-(U412-FD1-Pad0)") (class "Default")
      (node (ref "U412") (pin "0") (pinfunction "FD1_0") (pintype "passive"))
    )
    (net (code "185") (name "unconnected-(U412-FD2-Pad0)") (class "Default")
      (node (ref "U412") (pin "0") (pinfunction "FD2_0") (pintype "passive"))
    )
    (net (code "186") (name "unconnected-(U412-FD3-Pad0)") (class "Default")
      (node (ref "U412") (pin "0") (pinfunction "FD3_0") (pintype "passive"))
    )
    (net (code "187") (name "unconnected-(U412-FD4-Pad0)") (class "Default")
      (node (ref "U412") (pin "0") (pinfunction "FD4_0") (pintype "passive"))
    )
    (net (code "188") (name "unconnected-(U412-FD5-Pad0)") (class "Default")
      (node (ref "U412") (pin "0") (pinfunction "FD5_0") (pintype "passive"))
    )
    (net (code "189") (name "unconnected-(U412-FD6-Pad0)") (class "Default")
      (node (ref "U412") (pin "0") (pinfunction "FD6_0") (pintype "passive"))
    )
    (net (code "190") (name "unconnected-(U412-FD7-Pad0)") (class "Default")
      (node (ref "U412") (pin "0") (pinfunction "FD7_0") (pintype "passive"))
    )
    (net (code "191") (name "unconnected-(U412-FD8-Pad0)") (class "Default")
      (node (ref "U412") (pin "0") (pinfunction "FD8_0") (pintype "passive"))
    )
    (net (code "192") (name "unconnected-(U412-FD9-Pad0)") (class "Default")
      (node (ref "U412") (pin "0") (pinfunction "FD9_0") (pintype "passive"))
    )
    (net (code "193") (name "unconnected-(U412-FD10-Pad0)") (class "Default")
      (node (ref "U412") (pin "0") (pinfunction "FD10_0") (pintype "passive"))
    )
    (net (code "194") (name "unconnected-(U412-FD11-Pad0)") (class "Default")
      (node (ref "U412") (pin "0") (pinfunction "FD11_0") (pintype "passive"))
    )
    (net (code "195") (name "unconnected-(U412-FD12-Pad0)") (class "Default")
      (node (ref "U412") (pin "0") (pinfunction "FD12_0") (pintype "passive"))
    )
    (net (code "196") (name "unconnected-(U412-FD13-Pad0)") (class "Default")
      (node (ref "U412") (pin "0") (pinfunction "FD13_0") (pintype "passive"))
    )
    (net (code "197") (name "unconnected-(U412-FD14-Pad0)") (class "Default")
      (node (ref "U412") (pin "0") (pinfunction "FD14_0") (pintype "passive"))
    )
    (net (code "198") (name "unconnected-(U412-FD15-Pad0)") (class "Default")
      (node (ref "U412") (pin "0") (pinfunction "FD15_0") (pintype "passive"))
    )
    (net (code "199") (name "unconnected-(U412-IFCLK-Pad0)") (class "Default")
      (node (ref "U412") (pin "0") (pinfunction "IFCLK_0") (pintype "passive"))
    )
    (net (code "200") (name "unconnected-(U412-RDY0-Pad0)") (class "Default")
      (node (ref "U412") (pin "0") (pinfunction "RDY0_0") (pintype "passive"))
    )
    (net (code "201") (name "unconnected-(U412-RDY1-Pad0)") (class "Default")
      (node (ref "U412") (pin "0") (pinfunction "RDY1_0") (pintype "passive"))
    )
    (net (code "202") (name "unconnected-(U412-RDY2-Pad0)") (class "Default")
      (node (ref "U412") (pin "0") (pinfunction "RDY2_0") (pintype "passive"))
    )
    (net (code "203") (name "unconnected-(U412-RDY3-Pad0)") (class "Default")
      (node (ref "U412") (pin "0") (pinfunction "RDY3_0") (pintype "passive"))
    )
    (net (code "204") (name "unconnected-(U412-RDY4-Pad0)") (class "Default")
      (node (ref "U412") (pin "0") (pinfunction "RDY4_0") (pintype "passive"))
    )
    (net (code "205") (name "unconnected-(U412-RDY5-Pad0)") (class "Default")
      (node (ref "U412") (pin "0") (pinfunction "RDY5_0") (pintype "passive"))
    )
    (net (code "206") (name "unconnected-(U601-0-IOUTA-Pad0)") (class "Default")
      (node (ref "U601-0") (pin "0") (pinfunction "IOUTA_0") (pintype "passive"))
    )
    (net (code "207") (name "unconnected-(U601-0-IOUTA_2-Pad0)") (class "Default")
      (node (ref "U601-0") (pin "0") (pinfunction "IOUTA_2_0") (pintype "passive"))
    )
    (net (code "208") (name "unconnected-(U601-0-IOUTB-Pad0)") (class "Default")
      (node (ref "U601-0") (pin "0") (pinfunction "IOUTB_0") (pintype "passive"))
    )
    (net (code "209") (name "unconnected-(U601-0-IOUTB_2-Pad0)") (class "Default")
      (node (ref "U601-0") (pin "0") (pinfunction "IOUTB_2_0") (pintype "passive"))
    )
    (net (code "210") (name "unconnected-(U601-0-TX0-Pad0)") (class "Default")
      (node (ref "U601-0") (pin "0") (pinfunction "TX0_0") (pintype "passive"))
    )
    (net (code "211") (name "unconnected-(U601-0-TX1-Pad0)") (class "Default")
      (node (ref "U601-0") (pin "0") (pinfunction "TX1_0") (pintype "passive"))
    )
    (net (code "212") (name "unconnected-(U601-0-TX2-Pad0)") (class "Default")
      (node (ref "U601-0") (pin "0") (pinfunction "TX2_0") (pintype "passive"))
    )
    (net (code "213") (name "unconnected-(U601-0-TX3-Pad0)") (class "Default")
      (node (ref "U601-0") (pin "0") (pinfunction "TX3_0") (pintype "passive"))
    )
    (net (code "214") (name "unconnected-(U601-0-TX4-Pad0)") (class "Default")
      (node (ref "U601-0") (pin "0") (pinfunction "TX4_0") (pintype "passive"))
    )
    (net (code "215") (name "unconnected-(U601-0-TX5-Pad0)") (class "Default")
      (node (ref "U601-0") (pin "0") (pinfunction "TX5_0") (pintype "passive"))
    )
    (net (code "216") (name "unconnected-(U601-0-TX6-Pad0)") (class "Default")
      (node (ref "U601-0") (pin "0") (pinfunction "TX6_0") (pintype "passive"))
    )
    (net (code "217") (name "unconnected-(U601-0-TX7-Pad0)") (class "Default")
      (node (ref "U601-0") (pin "0") (pinfunction "TX7_0") (pintype "passive"))
    )
    (net (code "218") (name "unconnected-(U601-0-TX8-Pad0)") (class "Default")
      (node (ref "U601-0") (pin "0") (pinfunction "TX8_0") (pintype "passive"))
    )
    (net (code "219") (name "unconnected-(U601-0-TX9-Pad0)") (class "Default")
      (node (ref "U601-0") (pin "0") (pinfunction "TX9_0") (pintype "passive"))
    )
    (net (code "220") (name "unconnected-(U601-0-TX10-Pad0)") (class "Default")
      (node (ref "U601-0") (pin "0") (pinfunction "TX10_0") (pintype "passive"))
    )
    (net (code "221") (name "unconnected-(U601-0-TX11-Pad0)") (class "Default")
      (node (ref "U601-0") (pin "0") (pinfunction "TX11_0") (pintype "passive"))
    )
    (net (code "222") (name "unconnected-(U601-0-TX12-Pad0)") (class "Default")
      (node (ref "U601-0") (pin "0") (pinfunction "TX12_0") (pintype "passive"))
    )
    (net (code "223") (name "unconnected-(U601-0-TX13-Pad0)") (class "Default")
      (node (ref "U601-0") (pin "0") (pinfunction "TX13_0") (pintype "passive"))
    )
    (net (code "224") (name "unconnected-(U601-0-TXSYNC-Pad0)") (class "Default")
      (node (ref "U601-0") (pin "0") (pinfunction "TXSYNC_0") (pintype "passive"))
    )
    (net (code "225") (name "unconnected-(U601-DA0-Pad0)") (class "Default")
      (node (ref "U601") (pin "0") (pinfunction "DA0_0") (pintype "passive"))
    )
    (net (code "226") (name "unconnected-(U601-DA1-Pad0)") (class "Default")
      (node (ref "U601") (pin "0") (pinfunction "DA1_0") (pintype "passive"))
    )
    (net (code "227") (name "unconnected-(U601-DA2-Pad0)") (class "Default")
      (node (ref "U601") (pin "0") (pinfunction "DA2_0") (pintype "passive"))
    )
    (net (code "228") (name "unconnected-(U601-DA3-Pad0)") (class "Default")
      (node (ref "U601") (pin "0") (pinfunction "DA3_0") (pintype "passive"))
    )
    (net (code "229") (name "unconnected-(U601-DA4-Pad0)") (class "Default")
      (node (ref "U601") (pin "0") (pinfunction "DA4_0") (pintype "passive"))
    )
    (net (code "230") (name "unconnected-(U601-DA5-Pad0)") (class "Default")
      (node (ref "U601") (pin "0") (pinfunction "DA5_0") (pintype "passive"))
    )
    (net (code "231") (name "unconnected-(U601-DA6-Pad0)") (class "Default")
      (node (ref "U601") (pin "0") (pinfunction "DA6_0") (pintype "passive"))
    )
    (net (code "232") (name "unconnected-(U601-DA7-Pad0)") (class "Default")
      (node (ref "U601") (pin "0") (pinfunction "DA7_0") (pintype "passive"))
    )
    (net (code "233") (name "unconnected-(U601-DA8-Pad0)") (class "Default")
      (node (ref "U601") (pin "0") (pinfunction "DA8_0") (pintype "passive"))
    )
    (net (code "234") (name "unconnected-(U601-DA9-Pad0)") (class "Default")
      (node (ref "U601") (pin "0") (pinfunction "DA9_0") (pintype "passive"))
    )
    (net (code "235") (name "unconnected-(U601-DA10-Pad0)") (class "Default")
      (node (ref "U601") (pin "0") (pinfunction "DA10_0") (pintype "passive"))
    )
    (net (code "236") (name "unconnected-(U601-DA11-Pad0)") (class "Default")
      (node (ref "U601") (pin "0") (pinfunction "DA11_0") (pintype "passive"))
    )
    (net (code "237") (name "unconnected-(U601-DB0-Pad0)") (class "Default")
      (node (ref "U601") (pin "0") (pinfunction "DB0_0") (pintype "passive"))
    )
    (net (code "238") (name "unconnected-(U601-DB1-Pad0)") (class "Default")
      (node (ref "U601") (pin "0") (pinfunction "DB1_0") (pintype "passive"))
    )
    (net (code "239") (name "unconnected-(U601-DB2-Pad0)") (class "Default")
      (node (ref "U601") (pin "0") (pinfunction "DB2_0") (pintype "passive"))
    )
    (net (code "240") (name "unconnected-(U601-DB3-Pad0)") (class "Default")
      (node (ref "U601") (pin "0") (pinfunction "DB3_0") (pintype "passive"))
    )
    (net (code "241") (name "unconnected-(U601-DB4-Pad0)") (class "Default")
      (node (ref "U601") (pin "0") (pinfunction "DB4_0") (pintype "passive"))
    )
    (net (code "242") (name "unconnected-(U601-DB5-Pad0)") (class "Default")
      (node (ref "U601") (pin "0") (pinfunction "DB5_0") (pintype "passive"))
    )
    (net (code "243") (name "unconnected-(U601-DB6-Pad0)") (class "Default")
      (node (ref "U601") (pin "0") (pinfunction "DB6_0") (pintype "passive"))
    )
    (net (code "244") (name "unconnected-(U601-DB7-Pad0)") (class "Default")
      (node (ref "U601") (pin "0") (pinfunction "DB7_0") (pintype "passive"))
    )
    (net (code "245") (name "unconnected-(U601-DB8-Pad0)") (class "Default")
      (node (ref "U601") (pin "0") (pinfunction "DB8_0") (pintype "passive"))
    )
    (net (code "246") (name "unconnected-(U601-DB9-Pad0)") (class "Default")
      (node (ref "U601") (pin "0") (pinfunction "DB9_0") (pintype "passive"))
    )
    (net (code "247") (name "unconnected-(U601-DB10-Pad0)") (class "Default")
      (node (ref "U601") (pin "0") (pinfunction "DB10_0") (pintype "passive"))
    )
    (net (code "248") (name "unconnected-(U601-DB11-Pad0)") (class "Default")
      (node (ref "U601") (pin "0") (pinfunction "DB11_0") (pintype "passive"))
    )
    (net (code "249") (name "unconnected-(U601-RXSYNC-Pad0)") (class "Default")
      (node (ref "U601") (pin "0") (pinfunction "RXSYNC_0") (pintype "passive"))
    )
    (net (code "250") (name "unconnected-(U601-VINA-Pad0)") (class "Default")
      (node (ref "U601") (pin "0") (pinfunction "VINA_0") (pintype "passive"))
    )
    (net (code "251") (name "unconnected-(U601-VINA_2-Pad0)") (class "Default")
      (node (ref "U601") (pin "0") (pinfunction "VINA_2_0") (pintype "passive"))
    )
    (net (code "252") (name "unconnected-(U601-VINB-Pad0)") (class "Default")
      (node (ref "U601") (pin "0") (pinfunction "VINB_0") (pintype "passive"))
    )
    (net (code "253") (name "unconnected-(U601-VINB_2-Pad0)") (class "Default")
      (node (ref "U601") (pin "0") (pinfunction "VINB_2_0") (pintype "passive"))
    )
    (net (code "254") (name "unconnected-(U602-4-IOUTA-Pad0)") (class "Default")
      (node (ref "U602-4") (pin "0") (pinfunction "IOUTA_0") (pintype "passive"))
    )
    (net (code "255") (name "unconnected-(U602-4-IOUTA_2-Pad0)") (class "Default")
      (node (ref "U602-4") (pin "0") (pinfunction "IOUTA_2_0") (pintype "passive"))
    )
    (net (code "256") (name "unconnected-(U602-4-IOUTB-Pad0)") (class "Default")
      (node (ref "U602-4") (pin "0") (pinfunction "IOUTB_0") (pintype "passive"))
    )
    (net (code "257") (name "unconnected-(U602-4-IOUTB_2-Pad0)") (class "Default")
      (node (ref "U602-4") (pin "0") (pinfunction "IOUTB_2_0") (pintype "passive"))
    )
    (net (code "258") (name "unconnected-(U602-4-TX0-Pad0)") (class "Default")
      (node (ref "U602-4") (pin "0") (pinfunction "TX0_0") (pintype "passive"))
    )
    (net (code "259") (name "unconnected-(U602-4-TX1-Pad0)") (class "Default")
      (node (ref "U602-4") (pin "0") (pinfunction "TX1_0") (pintype "passive"))
    )
    (net (code "260") (name "unconnected-(U602-4-TX2-Pad0)") (class "Default")
      (node (ref "U602-4") (pin "0") (pinfunction "TX2_0") (pintype "passive"))
    )
    (net (code "261") (name "unconnected-(U602-4-TX3-Pad0)") (class "Default")
      (node (ref "U602-4") (pin "0") (pinfunction "TX3_0") (pintype "passive"))
    )
    (net (code "262") (name "unconnected-(U602-4-TX4-Pad0)") (class "Default")
      (node (ref "U602-4") (pin "0") (pinfunction "TX4_0") (pintype "passive"))
    )
    (net (code "263") (name "unconnected-(U602-4-TX5-Pad0)") (class "Default")
      (node (ref "U602-4") (pin "0") (pinfunction "TX5_0") (pintype "passive"))
    )
    (net (code "264") (name "unconnected-(U602-4-TX6-Pad0)") (class "Default")
      (node (ref "U602-4") (pin "0") (pinfunction "TX6_0") (pintype "passive"))
    )
    (net (code "265") (name "unconnected-(U602-4-TX7-Pad0)") (class "Default")
      (node (ref "U602-4") (pin "0") (pinfunction "TX7_0") (pintype "passive"))
    )
    (net (code "266") (name "unconnected-(U602-4-TX8-Pad0)") (class "Default")
      (node (ref "U602-4") (pin "0") (pinfunction "TX8_0") (pintype "passive"))
    )
    (net (code "267") (name "unconnected-(U602-4-TX9-Pad0)") (class "Default")
      (node (ref "U602-4") (pin "0") (pinfunction "TX9_0") (pintype "passive"))
    )
    (net (code "268") (name "unconnected-(U602-4-TX10-Pad0)") (class "Default")
      (node (ref "U602-4") (pin "0") (pinfunction "TX10_0") (pintype "passive"))
    )
    (net (code "269") (name "unconnected-(U602-4-TX11-Pad0)") (class "Default")
      (node (ref "U602-4") (pin "0") (pinfunction "TX11_0") (pintype "passive"))
    )
    (net (code "270") (name "unconnected-(U602-4-TX12-Pad0)") (class "Default")
      (node (ref "U602-4") (pin "0") (pinfunction "TX12_0") (pintype "passive"))
    )
    (net (code "271") (name "unconnected-(U602-4-TX13-Pad0)") (class "Default")
      (node (ref "U602-4") (pin "0") (pinfunction "TX13_0") (pintype "passive"))
    )
    (net (code "272") (name "unconnected-(U602-4-TXSYNC-Pad0)") (class "Default")
      (node (ref "U602-4") (pin "0") (pinfunction "TXSYNC_0") (pintype "passive"))
    )
    (net (code "273") (name "unconnected-(U602-DA0-Pad0)") (class "Default")
      (node (ref "U602") (pin "0") (pinfunction "DA0_0") (pintype "passive"))
    )
    (net (code "274") (name "unconnected-(U602-DA1-Pad0)") (class "Default")
      (node (ref "U602") (pin "0") (pinfunction "DA1_0") (pintype "passive"))
    )
    (net (code "275") (name "unconnected-(U602-DA2-Pad0)") (class "Default")
      (node (ref "U602") (pin "0") (pinfunction "DA2_0") (pintype "passive"))
    )
    (net (code "276") (name "unconnected-(U602-DA3-Pad0)") (class "Default")
      (node (ref "U602") (pin "0") (pinfunction "DA3_0") (pintype "passive"))
    )
    (net (code "277") (name "unconnected-(U602-DA4-Pad0)") (class "Default")
      (node (ref "U602") (pin "0") (pinfunction "DA4_0") (pintype "passive"))
    )
    (net (code "278") (name "unconnected-(U602-DA5-Pad0)") (class "Default")
      (node (ref "U602") (pin "0") (pinfunction "DA5_0") (pintype "passive"))
    )
    (net (code "279") (name "unconnected-(U602-DA6-Pad0)") (class "Default")
      (node (ref "U602") (pin "0") (pinfunction "DA6_0") (pintype "passive"))
    )
    (net (code "280") (name "unconnected-(U602-DA7-Pad0)") (class "Default")
      (node (ref "U602") (pin "0") (pinfunction "DA7_0") (pintype "passive"))
    )
    (net (code "281") (name "unconnected-(U602-DA8-Pad0)") (class "Default")
      (node (ref "U602") (pin "0") (pinfunction "DA8_0") (pintype "passive"))
    )
    (net (code "282") (name "unconnected-(U602-DA9-Pad0)") (class "Default")
      (node (ref "U602") (pin "0") (pinfunction "DA9_0") (pintype "passive"))
    )
    (net (code "283") (name "unconnected-(U602-DA10-Pad0)") (class "Default")
      (node (ref "U602") (pin "0") (pinfunction "DA10_0") (pintype "passive"))
    )
    (net (code "284") (name "unconnected-(U602-DA11-Pad0)") (class "Default")
      (node (ref "U602") (pin "0") (pinfunction "DA11_0") (pintype "passive"))
    )
    (net (code "285") (name "unconnected-(U602-DB0-Pad0)") (class "Default")
      (node (ref "U602") (pin "0") (pinfunction "DB0_0") (pintype "passive"))
    )
    (net (code "286") (name "unconnected-(U602-DB1-Pad0)") (class "Default")
      (node (ref "U602") (pin "0") (pinfunction "DB1_0") (pintype "passive"))
    )
    (net (code "287") (name "unconnected-(U602-DB2-Pad0)") (class "Default")
      (node (ref "U602") (pin "0") (pinfunction "DB2_0") (pintype "passive"))
    )
    (net (code "288") (name "unconnected-(U602-DB3-Pad0)") (class "Default")
      (node (ref "U602") (pin "0") (pinfunction "DB3_0") (pintype "passive"))
    )
    (net (code "289") (name "unconnected-(U602-DB4-Pad0)") (class "Default")
      (node (ref "U602") (pin "0") (pinfunction "DB4_0") (pintype "passive"))
    )
    (net (code "290") (name "unconnected-(U602-DB5-Pad0)") (class "Default")
      (node (ref "U602") (pin "0") (pinfunction "DB5_0") (pintype "passive"))
    )
    (net (code "291") (name "unconnected-(U602-DB6-Pad0)") (class "Default")
      (node (ref "U602") (pin "0") (pinfunction "DB6_0") (pintype "passive"))
    )
    (net (code "292") (name "unconnected-(U602-DB7-Pad0)") (class "Default")
      (node (ref "U602") (pin "0") (pinfunction "DB7_0") (pintype "passive"))
    )
    (net (code "293") (name "unconnected-(U602-DB8-Pad0)") (class "Default")
      (node (ref "U602") (pin "0") (pinfunction "DB8_0") (pintype "passive"))
    )
    (net (code "294") (name "unconnected-(U602-DB9-Pad0)") (class "Default")
      (node (ref "U602") (pin "0") (pinfunction "DB9_0") (pintype "passive"))
    )
    (net (code "295") (name "unconnected-(U602-DB10-Pad0)") (class "Default")
      (node (ref "U602") (pin "0") (pinfunction "DB10_0") (pintype "passive"))
    )
    (net (code "296") (name "unconnected-(U602-DB11-Pad0)") (class "Default")
      (node (ref "U602") (pin "0") (pinfunction "DB11_0") (pintype "passive"))
    )
    (net (code "297") (name "unconnected-(U602-RXSYNC-Pad0)") (class "Default")
      (node (ref "U602") (pin "0") (pinfunction "RXSYNC_0") (pintype "passive"))
    )
    (net (code "298") (name "unconnected-(U602-VINA-Pad0)") (class "Default")
      (node (ref "U602") (pin "0") (pinfunction "VINA_0") (pintype "passive"))
    )
    (net (code "299") (name "unconnected-(U602-VINA_2-Pad0)") (class "Default")
      (node (ref "U602") (pin "0") (pinfunction "VINA_2_0") (pintype "passive"))
    )
    (net (code "300") (name "unconnected-(U602-VINB-Pad0)") (class "Default")
      (node (ref "U602") (pin "0") (pinfunction "VINB_0") (pintype "passive"))
    )
    (net (code "301") (name "unconnected-(U602-VINB_2-Pad0)") (class "Default")
      (node (ref "U602") (pin "0") (pinfunction "VINB_2_0") (pintype "passive"))
    )
  )
)
